# MCU.net
KiCad netlist of a schematic drawn in Altium Designer
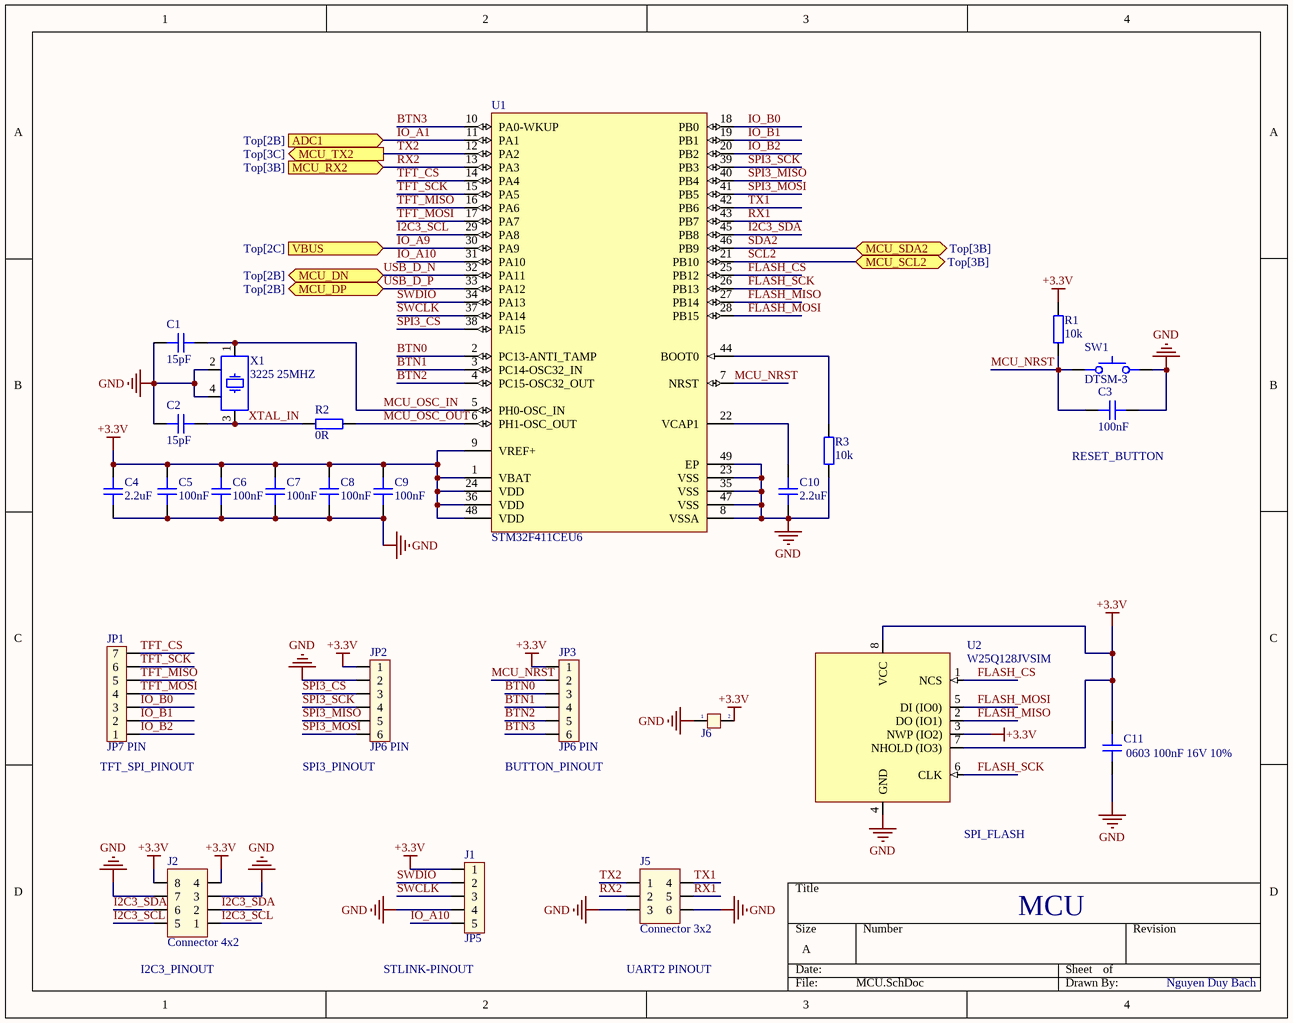
[diagram p0: MCU.SchDoc]

(export (version "E")
  (design (tool "Eeschema 10.0.6"))
  (components
    (comp (ref "C1")
      (value "15pF")
      (footprint "CAP_0603")
      (description "Capacitor SMD 0603")
      (libsource (lib "Project") (part "CAP_0603"))
    )
    (comp (ref "C2")
      (value "15pF")
      (footprint "CAP_0603")
      (description "Capacitor SMD 0603")
      (libsource (lib "Project") (part "CAP_0603"))
    )
    (comp (ref "C3")
      (value "100nF")
      (footprint "CAP_0603")
      (description "Capacitor SMD 0603")
      (libsource (lib "Project") (part "CAP_0603"))
    )
    (comp (ref "C4")
      (value "2.2uF")
      (footprint "CAP_0805")
      (description "Capacitor SMD 0805")
      (libsource (lib "Project") (part "CAP_0805"))
    )
    (comp (ref "C5")
      (value "100nF")
      (footprint "CAP_0603")
      (description "Capacitor SMD 0603")
      (libsource (lib "Project") (part "CAP_0603"))
    )
    (comp (ref "C6")
      (value "100nF")
      (footprint "CAP_0603")
      (description "Capacitor SMD 0603")
      (libsource (lib "Project") (part "CAP_0603"))
    )
    (comp (ref "C7")
      (value "100nF")
      (footprint "CAP_0603")
      (description "Capacitor SMD 0603")
      (libsource (lib "Project") (part "CAP_0603"))
    )
    (comp (ref "C8")
      (value "100nF")
      (footprint "CAP_0603")
      (description "Capacitor SMD 0603")
      (libsource (lib "Project") (part "CAP_0603"))
    )
    (comp (ref "C9")
      (value "100nF")
      (footprint "CAP_0603")
      (description "Capacitor SMD 0603")
      (libsource (lib "Project") (part "CAP_0603"))
    )
    (comp (ref "C10")
      (value "2.2uF")
      (footprint "CAP_0805")
      (description "Capacitor SMD 0805")
      (libsource (lib "Project") (part "CAP_0805"))
    )
    (comp (ref "C11")
      (value "0603 100nF 16V 10%")
      (footprint "CAP_0603")
      (description "Capacitor SMD 0603")
      (libsource (lib "Schematic-Lib-PhilsLab") (part "CAP_0603"))
    )
    (comp (ref "J1") (value "JP5") (footprint "JP5") (libsource (lib "syhaunguyen") (part "JP5")))
    (comp (ref "J2")
      (value "Connector 4x2")
      (footprint "JP4x2")
      (libsource (lib "syhaunguyen") (part "JP4x2"))
    )
    (comp (ref "J5")
      (value "Connector 3x2")
      (footprint "JP3x2")
      (libsource (lib "syhaunguyen") (part "JP3x2"))
    )
    (comp (ref "J6") (value "Jumper 2") (footprint "JP2") (libsource (lib "syhaunguyen") (part "JP 2")))
    (comp (ref "JP1") (value "JP7 PIN") (footprint "JP7") (libsource (lib "syhaunguyen") (part "JP7")))
    (comp (ref "JP2") (value "JP6 PIN") (footprint "JP6") (libsource (lib "syhaunguyen") (part "JP6")))
    (comp (ref "JP3") (value "JP6 PIN") (footprint "JP6") (libsource (lib "syhaunguyen") (part "JP6")))
    (comp (ref "R1")
      (value "10k")
      (footprint "RES_0603")
      (description "Resistor SMD 0603")
      (libsource (lib "Project") (part "RES_0603"))
    )
    (comp (ref "R2")
      (value "0R")
      (footprint "RES_0603")
      (description "Resistor SMD 0603")
      (libsource (lib "Project") (part "RES_0603"))
    )
    (comp (ref "R3")
      (value "10k")
      (footprint "RES_0603")
      (description "Resistor SMD 0603")
      (libsource (lib "Project") (part "RES_0603"))
    )
    (comp (ref "SW1")
      (value "DTSM-3")
      (footprint "DTSM-3")
      (description "Tactile Switch SMD SPST")
      (fields (field (name "MANUFACTURER") "Diptronics"))
      (libsource (lib "Schematic-Lib-PhilsLab") (part "DTSM-3"))
    )
    (comp (ref "U1")
      (value "STM32F411CEU6")
      (footprint "STM-UFQFPN48_L")
      (libsource (lib "Altium Content Vault") (part "MC-ARM-STM32F411-UFQFPN48"))
    )
    (comp (ref "U2")
      (value "W25Q128JVSIM")
      (footprint "SOIC-8")
      (description "128M-BIT\r\nSERIAL FLASH MEMORY WITH\r\nDUAL/QUAD SPI & QPI & DTR SOIC-8")
      (fields (field (name "MANUFACTURER") "Winbond"))
      (libsource (lib "Project") (part "W25Q128JVSIM"))
    )
    (comp (ref "X1")
      (value "3225 25MHZ")
      (footprint "XTAL_3225")
      (description "Crystal Oscillator")
      (libsource (lib "Project") (part "XTAL 4 Pin"))
    )
  )
  (nets
    (net (code "1") (name "+3.3V") (class "Default")
      (node (ref "C11") (pin "2") (pinfunction "2_2") (pintype "passive"))
      (node (ref "C4") (pin "2") (pinfunction "2_2") (pintype "passive"))
      (node (ref "C5") (pin "2") (pinfunction "2_2") (pintype "passive"))
      (node (ref "C6") (pin "2") (pinfunction "2_2") (pintype "passive"))
      (node (ref "C7") (pin "2") (pinfunction "2_2") (pintype "passive"))
      (node (ref "C8") (pin "2") (pinfunction "2_2") (pintype "passive"))
      (node (ref "C9") (pin "2") (pinfunction "2_2") (pintype "passive"))
      (node (ref "J1") (pin "1") (pinfunction "1_1") (pintype "passive"))
      (node (ref "J2") (pin "4") (pinfunction "4_4") (pintype "passive"))
      (node (ref "J2") (pin "8") (pinfunction "8_8") (pintype "passive"))
      (node (ref "J6") (pin "2") (pinfunction "2_2") (pintype "passive"))
      (node (ref "JP2") (pin "1") (pinfunction "1_1") (pintype "passive"))
      (node (ref "JP3") (pin "1") (pinfunction "1_1") (pintype "passive"))
      (node (ref "R1") (pin "2") (pinfunction "2_2") (pintype "passive"))
      (node (ref "U1") (pin "1") (pinfunction "VBAT_1") (pintype "power_in"))
      (node (ref "U1") (pin "24") (pinfunction "VDD_24") (pintype "power_in"))
      (node (ref "U1") (pin "36") (pinfunction "VDD_36") (pintype "power_in"))
      (node (ref "U1") (pin "48") (pinfunction "VDD_48") (pintype "power_in"))
      (node (ref "U1") (pin "9") (pinfunction "VREF+_9") (pintype "power_in"))
      (node (ref "U2") (pin "3") (pinfunction "NWP_(IO2)_3") (pintype "bidirectional"))
      (node (ref "U2") (pin "7") (pinfunction "NHOLD_(IO3)_7") (pintype "bidirectional"))
      (node (ref "U2") (pin "8") (pinfunction "VCC_8") (pintype "power_in"))
    )
    (net (code "2") (name "/BTN0") (class "Default")
      (node (ref "JP3") (pin "3") (pinfunction "3_3") (pintype "passive"))
      (node (ref "U1") (pin "2") (pinfunction "PC13-ANTI_TAMP_2") (pintype "bidirectional"))
    )
    (net (code "3") (name "/BTN1") (class "Default")
      (node (ref "JP3") (pin "4") (pinfunction "4_4") (pintype "passive"))
      (node (ref "U1") (pin "3") (pinfunction "PC14-OSC32_IN_3") (pintype "bidirectional"))
    )
    (net (code "4") (name "/BTN2") (class "Default")
      (node (ref "JP3") (pin "5") (pinfunction "5_5") (pintype "passive"))
      (node (ref "U1") (pin "4") (pinfunction "PC15-OSC32_OUT_4") (pintype "bidirectional"))
    )
    (net (code "5") (name "/BTN3") (class "Default")
      (node (ref "JP3") (pin "6") (pinfunction "6_6") (pintype "passive"))
      (node (ref "U1") (pin "10") (pinfunction "PA0-WKUP_10") (pintype "bidirectional"))
    )
    (net (code "6") (name "/FLASH_CS") (class "Default")
      (node (ref "U1") (pin "25") (pinfunction "PB12_25") (pintype "bidirectional"))
      (node (ref "U2") (pin "1") (pinfunction "NCS_1") (pintype "input"))
    )
    (net (code "7") (name "/FLASH_MISO") (class "Default")
      (node (ref "U1") (pin "27") (pinfunction "PB14_27") (pintype "bidirectional"))
      (node (ref "U2") (pin "2") (pinfunction "DO_(IO1)_2") (pintype "bidirectional"))
    )
    (net (code "8") (name "/FLASH_MOSI") (class "Default")
      (node (ref "U1") (pin "28") (pinfunction "PB15_28") (pintype "bidirectional"))
      (node (ref "U2") (pin "5") (pinfunction "DI_(IO0)_5") (pintype "bidirectional"))
    )
    (net (code "9") (name "/FLASH_SCK") (class "Default")
      (node (ref "U1") (pin "26") (pinfunction "PB13_26") (pintype "bidirectional"))
      (node (ref "U2") (pin "6") (pinfunction "CLK_6") (pintype "input"))
    )
    (net (code "10") (name "/I2C3_SCL") (class "Default")
      (node (ref "J2") (pin "1") (pinfunction "1_1") (pintype "passive"))
      (node (ref "J2") (pin "5") (pinfunction "5_5") (pintype "passive"))
      (node (ref "U1") (pin "29") (pinfunction "PA8_29") (pintype "bidirectional"))
    )
    (net (code "11") (name "/I2C3_SDA") (class "Default")
      (node (ref "J2") (pin "2") (pinfunction "2_2") (pintype "passive"))
      (node (ref "J2") (pin "6") (pinfunction "6_6") (pintype "passive"))
      (node (ref "U1") (pin "45") (pinfunction "PB8_45") (pintype "bidirectional"))
    )
    (net (code "12") (name "/IO_A1") (class "Default")
      (node (ref "U1") (pin "11") (pinfunction "PA1_11") (pintype "bidirectional"))
    )
    (net (code "13") (name "/IO_A9") (class "Default")
      (node (ref "U1") (pin "30") (pinfunction "PA9_30") (pintype "bidirectional"))
    )
    (net (code "14") (name "/IO_A10") (class "Default")
      (node (ref "J1") (pin "5") (pinfunction "5_5") (pintype "passive"))
      (node (ref "U1") (pin "31") (pinfunction "PA10_31") (pintype "bidirectional"))
    )
    (net (code "15") (name "/IO_B0") (class "Default")
      (node (ref "JP1") (pin "3") (pinfunction "3_3") (pintype "passive"))
      (node (ref "U1") (pin "18") (pinfunction "PB0_18") (pintype "bidirectional"))
    )
    (net (code "16") (name "/IO_B1") (class "Default")
      (node (ref "JP1") (pin "2") (pinfunction "2_2") (pintype "passive"))
      (node (ref "U1") (pin "19") (pinfunction "PB1_19") (pintype "bidirectional"))
    )
    (net (code "17") (name "/IO_B2") (class "Default")
      (node (ref "JP1") (pin "1") (pinfunction "1_1") (pintype "passive"))
      (node (ref "U1") (pin "20") (pinfunction "PB2_20") (pintype "bidirectional"))
    )
    (net (code "18") (name "/MCU_NRST") (class "Default")
      (node (ref "C3") (pin "2") (pinfunction "2_2") (pintype "passive"))
      (node (ref "JP3") (pin "2") (pinfunction "2_2") (pintype "passive"))
      (node (ref "R1") (pin "1") (pinfunction "1_1") (pintype "passive"))
      (node (ref "SW1") (pin "1") (pintype "passive"))
      (node (ref "U1") (pin "7") (pinfunction "NRST_7") (pintype "bidirectional"))
    )
    (net (code "19") (name "/MCU_OSC_IN") (class "Default")
      (node (ref "C1") (pin "1") (pinfunction "1_1") (pintype "passive"))
      (node (ref "U1") (pin "5") (pinfunction "PH0-OSC_IN_5") (pintype "bidirectional"))
      (node (ref "X1") (pin "1") (pinfunction "1_1") (pintype "passive"))
    )
    (net (code "20") (name "/MCU_OSC_OUT") (class "Default")
      (node (ref "R2") (pin "1") (pinfunction "1_1") (pintype "passive"))
      (node (ref "U1") (pin "6") (pinfunction "PH1-OSC_OUT_6") (pintype "bidirectional"))
    )
    (net (code "21") (name "/RX1") (class "Default")
      (node (ref "J5") (pin "5") (pinfunction "5_5") (pintype "passive"))
      (node (ref "U1") (pin "43") (pinfunction "PB7_43") (pintype "bidirectional"))
    )
    (net (code "22") (name "/RX2") (class "Default")
      (node (ref "J5") (pin "2") (pinfunction "2_2") (pintype "passive"))
      (node (ref "U1") (pin "13") (pinfunction "PA3_13") (pintype "bidirectional"))
    )
    (net (code "23") (name "/SCL2") (class "Default")
      (node (ref "U1") (pin "21") (pinfunction "PB10_21") (pintype "bidirectional"))
    )
    (net (code "24") (name "/SDA2") (class "Default")
      (node (ref "U1") (pin "46") (pinfunction "PB9_46") (pintype "bidirectional"))
    )
    (net (code "25") (name "/SPI3_CS") (class "Default")
      (node (ref "JP2") (pin "3") (pinfunction "3_3") (pintype "passive"))
      (node (ref "U1") (pin "38") (pinfunction "PA15_38") (pintype "bidirectional"))
    )
    (net (code "26") (name "/SPI3_MISO") (class "Default")
      (node (ref "JP2") (pin "5") (pinfunction "5_5") (pintype "passive"))
      (node (ref "U1") (pin "40") (pinfunction "PB4_40") (pintype "bidirectional"))
    )
    (net (code "27") (name "/SPI3_MOSI") (class "Default")
      (node (ref "JP2") (pin "6") (pinfunction "6_6") (pintype "passive"))
      (node (ref "U1") (pin "41") (pinfunction "PB5_41") (pintype "bidirectional"))
    )
    (net (code "28") (name "/SPI3_SCK") (class "Default")
      (node (ref "JP2") (pin "4") (pinfunction "4_4") (pintype "passive"))
      (node (ref "U1") (pin "39") (pinfunction "PB3_39") (pintype "bidirectional"))
    )
    (net (code "29") (name "/SWCLK") (class "Default")
      (node (ref "J1") (pin "3") (pinfunction "3_3") (pintype "passive"))
      (node (ref "U1") (pin "37") (pinfunction "PA14_37") (pintype "bidirectional"))
    )
    (net (code "30") (name "/SWDIO") (class "Default")
      (node (ref "J1") (pin "2") (pinfunction "2_2") (pintype "passive"))
      (node (ref "U1") (pin "34") (pinfunction "PA13_34") (pintype "bidirectional"))
    )
    (net (code "31") (name "/TFT_CS") (class "Default")
      (node (ref "JP1") (pin "7") (pinfunction "7_7") (pintype "passive"))
      (node (ref "U1") (pin "14") (pinfunction "PA4_14") (pintype "bidirectional"))
    )
    (net (code "32") (name "/TFT_MISO") (class "Default")
      (node (ref "JP1") (pin "5") (pinfunction "5_5") (pintype "passive"))
      (node (ref "U1") (pin "16") (pinfunction "PA6_16") (pintype "bidirectional"))
    )
    (net (code "33") (name "/TFT_MOSI") (class "Default")
      (node (ref "JP1") (pin "4") (pinfunction "4_4") (pintype "passive"))
      (node (ref "U1") (pin "17") (pinfunction "PA7_17") (pintype "bidirectional"))
    )
    (net (code "34") (name "/TFT_SCK") (class "Default")
      (node (ref "JP1") (pin "6") (pinfunction "6_6") (pintype "passive"))
      (node (ref "U1") (pin "15") (pinfunction "PA5_15") (pintype "bidirectional"))
    )
    (net (code "35") (name "/TX1") (class "Default")
      (node (ref "J5") (pin "4") (pinfunction "4_4") (pintype "passive"))
      (node (ref "U1") (pin "42") (pinfunction "PB6_42") (pintype "bidirectional"))
    )
    (net (code "36") (name "/TX2") (class "Default")
      (node (ref "J5") (pin "1") (pinfunction "1_1") (pintype "passive"))
      (node (ref "U1") (pin "12") (pinfunction "PA2_12") (pintype "bidirectional"))
    )
    (net (code "37") (name "/USB_D_N") (class "Default")
      (node (ref "U1") (pin "32") (pinfunction "PA11_32") (pintype "bidirectional"))
    )
    (net (code "38") (name "/USB_D_P") (class "Default")
      (node (ref "U1") (pin "33") (pinfunction "PA12_33") (pintype "bidirectional"))
    )
    (net (code "39") (name "/XTAL_IN") (class "Default")
      (node (ref "C2") (pin "1") (pinfunction "1_1") (pintype "passive"))
      (node (ref "R2") (pin "2") (pinfunction "2_2") (pintype "passive"))
      (node (ref "X1") (pin "3") (pinfunction "3_3") (pintype "passive"))
    )
    (net (code "40") (name "GND") (class "Default")
      (node (ref "C1") (pin "2") (pinfunction "2_2") (pintype "passive"))
      (node (ref "C10") (pin "1") (pinfunction "1_1") (pintype "passive"))
      (node (ref "C11") (pin "1") (pinfunction "1_1") (pintype "passive"))
      (node (ref "C2") (pin "2") (pinfunction "2_2") (pintype "passive"))
      (node (ref "C3") (pin "1") (pinfunction "1_1") (pintype "passive"))
      (node (ref "C4") (pin "1") (pinfunction "1_1") (pintype "passive"))
      (node (ref "C5") (pin "1") (pinfunction "1_1") (pintype "passive"))
      (node (ref "C6") (pin "1") (pinfunction "1_1") (pintype "passive"))
      (node (ref "C7") (pin "1") (pinfunction "1_1") (pintype "passive"))
      (node (ref "C8") (pin "1") (pinfunction "1_1") (pintype "passive"))
      (node (ref "C9") (pin "1") (pinfunction "1_1") (pintype "passive"))
      (node (ref "J1") (pin "4") (pinfunction "4_4") (pintype "passive"))
      (node (ref "J2") (pin "3") (pinfunction "3_3") (pintype "passive"))
      (node (ref "J2") (pin "7") (pinfunction "7_7") (pintype "passive"))
      (node (ref "J5") (pin "3") (pinfunction "3_3") (pintype "passive"))
      (node (ref "J5") (pin "6") (pinfunction "6_6") (pintype "passive"))
      (node (ref "J6") (pin "1") (pinfunction "1_1") (pintype "passive"))
      (node (ref "JP2") (pin "2") (pinfunction "2_2") (pintype "passive"))
      (node (ref "R3") (pin "1") (pinfunction "1_1") (pintype "passive"))
      (node (ref "SW1") (pin "2") (pintype "passive"))
      (node (ref "U1") (pin "23") (pinfunction "VSS_23") (pintype "power_in"))
      (node (ref "U1") (pin "35") (pinfunction "VSS_35") (pintype "power_in"))
      (node (ref "U1") (pin "47") (pinfunction "VSS_47") (pintype "power_in"))
      (node (ref "U1") (pin "49") (pinfunction "EP_49") (pintype "power_in"))
      (node (ref "U1") (pin "8") (pinfunction "VSSA_8") (pintype "power_in"))
      (node (ref "U2") (pin "4") (pinfunction "GND_4") (pintype "power_in"))
      (node (ref "X1") (pin "2") (pinfunction "2_2") (pintype "passive"))
      (node (ref "X1") (pin "4") (pinfunction "4_4") (pintype "passive"))
    )
    (net (code "41") (name "Net-(U1-BOOT0)") (class "Default")
      (node (ref "R3") (pin "2") (pinfunction "2_2") (pintype "passive"))
      (node (ref "U1") (pin "44") (pinfunction "BOOT0_44") (pintype "input"))
    )
    (net (code "42") (name "Net-(U1-VCAP1)") (class "Default")
      (node (ref "C10") (pin "2") (pinfunction "2_2") (pintype "passive"))
      (node (ref "U1") (pin "22") (pinfunction "VCAP1_22") (pintype "passive"))
    )
  )
)
